# displayLCD.net
KiCad netlist of a schematic drawn in Altium Designer
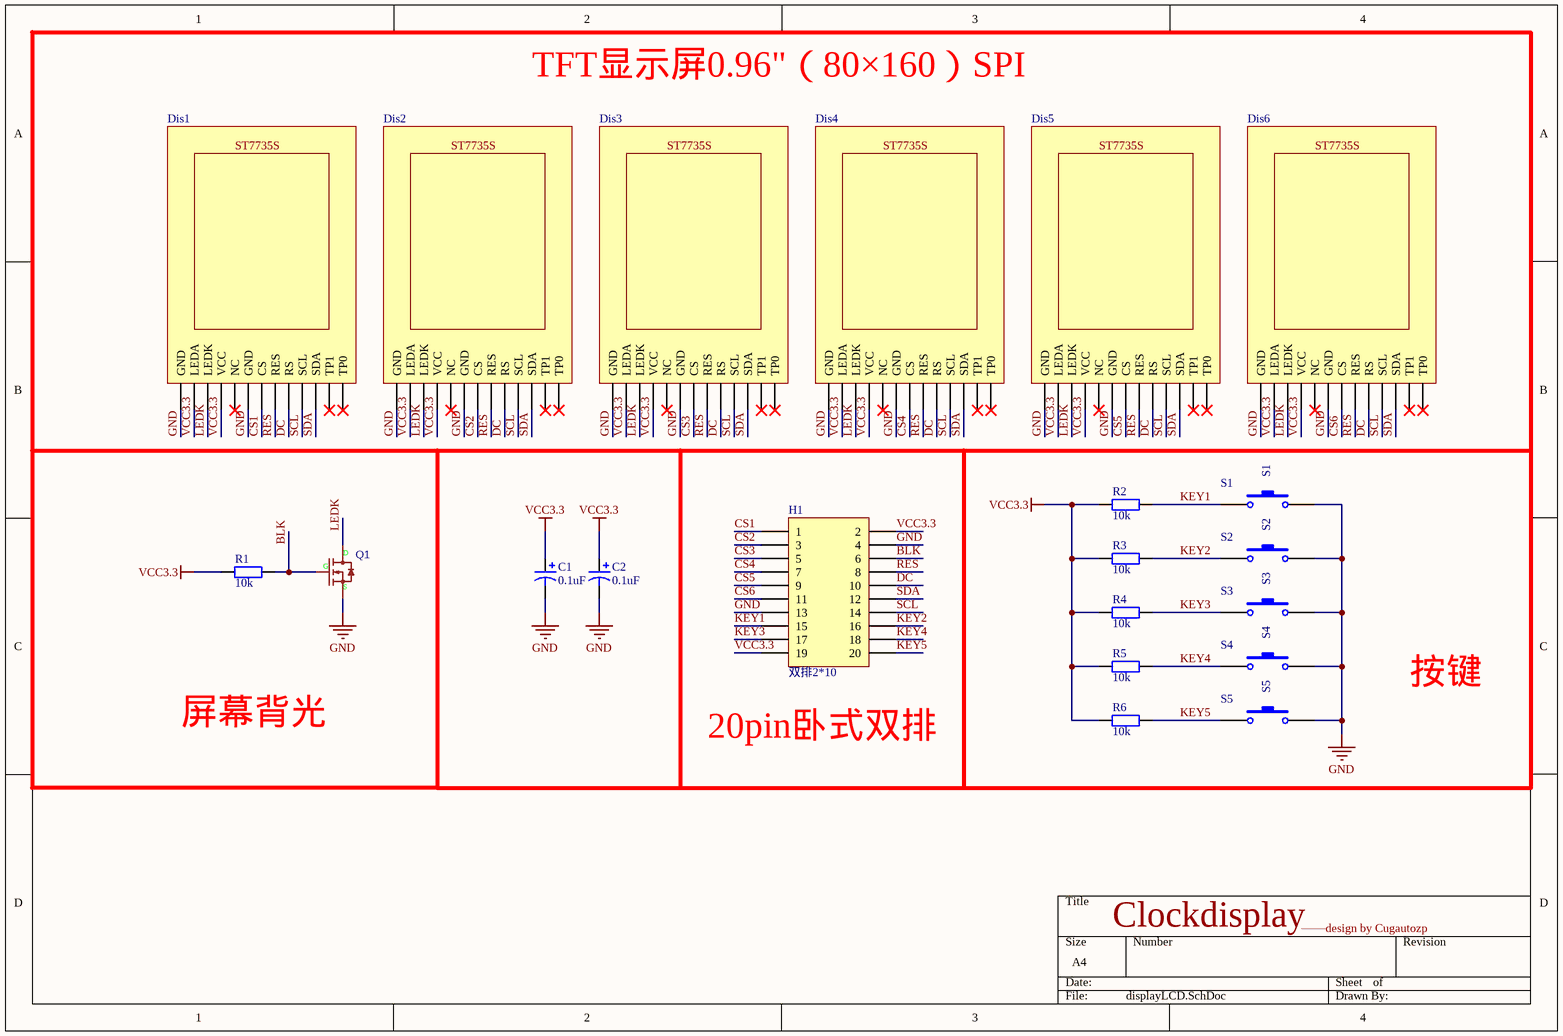
[diagram p0: displayLCD.SchDoc]

(export (version "E")
  (design (tool "Eeschema 10.0.6"))
  (components
    (comp (ref "C1")
      (value "0.1uF")
      (footprint "Cap0603")
      (description "Polarized Capacitor (Surface Mount)")
      (fields (field (name "PUBLISHER") "Altium Limited"))
      (libsource (lib "Miscellaneous Devices") (part "Cap Pol3"))
    )
    (comp (ref "C2")
      (value "0.1uF")
      (footprint "Cap0603")
      (description "Polarized Capacitor (Surface Mount)")
      (fields (field (name "PUBLISHER") "Altium Limited"))
      (libsource (lib "Miscellaneous Devices") (part "Cap Pol3"))
    )
    (comp (ref "Dis1")
      (value "LCD80*160")
      (footprint "LCD屏80*160")
      (libsource (lib "displayLCD") (part "LCD80*160"))
    )
    (comp (ref "Dis2")
      (value "LCD80*160")
      (footprint "LCD屏80*160")
      (libsource (lib "displayLCD") (part "LCD80*160"))
    )
    (comp (ref "Dis3")
      (value "LCD80*160")
      (footprint "LCD屏80*160")
      (libsource (lib "displayLCD") (part "LCD80*160"))
    )
    (comp (ref "Dis4")
      (value "LCD80*160")
      (footprint "LCD屏80*160")
      (libsource (lib "displayLCD") (part "LCD80*160"))
    )
    (comp (ref "Dis5")
      (value "LCD80*160")
      (footprint "LCD屏80*160")
      (libsource (lib "displayLCD") (part "LCD80*160"))
    )
    (comp (ref "Dis6")
      (value "LCD80*160")
      (footprint "LCD屏80*160")
      (libsource (lib "displayLCD") (part "LCD80*160"))
    )
    (comp (ref "H1") (value "双排2*10") (footprint "pin20双排母") (libsource (lib "displayLCD") (part "双排2*10")))
    (comp (ref "Q1")
      (value "LN4812LT1G")
      (footprint "sot23")
      (fields (field (name "BOM_SUPPLIER PART") "C559076") (field (name "CONTRIBUTOR") "LCSC"))
      (libsource (lib "displayLCD") (part "LN4812LT1G"))
    )
    (comp (ref "R1")
      (value "10k")
      (footprint "R0603")
      (description "Resistor")
      (fields (field (name "PUBLISHER") "Altium Limited"))
      (libsource (lib "Miscellaneous Devices") (part "Res2"))
    )
    (comp (ref "R2")
      (value "10k")
      (footprint "R0603")
      (description "Resistor")
      (fields (field (name "PUBLISHER") "Altium Limited"))
      (libsource (lib "Miscellaneous Devices") (part "Res2"))
    )
    (comp (ref "R3")
      (value "10k")
      (footprint "R0603")
      (description "Resistor")
      (fields (field (name "PUBLISHER") "Altium Limited"))
      (libsource (lib "Miscellaneous Devices") (part "Res2"))
    )
    (comp (ref "R4")
      (value "10k")
      (footprint "R0603")
      (description "Resistor")
      (fields (field (name "PUBLISHER") "Altium Limited"))
      (libsource (lib "Miscellaneous Devices") (part "Res2"))
    )
    (comp (ref "R5")
      (value "10k")
      (footprint "R0603")
      (description "Resistor")
      (fields (field (name "PUBLISHER") "Altium Limited"))
      (libsource (lib "Miscellaneous Devices") (part "Res2"))
    )
    (comp (ref "R6")
      (value "10k")
      (footprint "R0603")
      (description "Resistor")
      (fields (field (name "PUBLISHER") "Altium Limited"))
      (libsource (lib "Miscellaneous Devices") (part "Res2"))
    )
    (comp (ref "S1")
      (value "S1")
      (footprint "key(按键)")
      (description "Switch")
      (fields (field (name "PUBLISHER") "Altium Limited"))
      (libsource (lib "Miscellaneous Devices") (part "SW-PB"))
    )
    (comp (ref "S2")
      (value "S2")
      (footprint "key(按键)")
      (description "Switch")
      (fields (field (name "PUBLISHER") "Altium Limited"))
      (libsource (lib "Miscellaneous Devices") (part "SW-PB"))
    )
    (comp (ref "S3")
      (value "S3")
      (footprint "key(按键)")
      (description "Switch")
      (fields (field (name "PUBLISHER") "Altium Limited"))
      (libsource (lib "Miscellaneous Devices") (part "SW-PB"))
    )
    (comp (ref "S4")
      (value "S4")
      (footprint "key(按键)")
      (description "Switch")
      (fields (field (name "PUBLISHER") "Altium Limited"))
      (libsource (lib "Miscellaneous Devices") (part "SW-PB"))
    )
    (comp (ref "S5")
      (value "S5")
      (footprint "key(按键)")
      (description "Switch")
      (fields (field (name "PUBLISHER") "Altium Limited"))
      (libsource (lib "Miscellaneous Devices") (part "SW-PB"))
    )
  )
  (nets
    (net (code "1") (name "/BLK") (class "Default")
      (node (ref "H1") (pin "6") (pinfunction "6_6") (pintype "passive"))
      (node (ref "Q1") (pin "1") (pinfunction "G_1") (pintype "passive"))
      (node (ref "R1") (pin "2") (pinfunction "2_2") (pintype "passive"))
    )
    (net (code "2") (name "/CS1") (class "Default")
      (node (ref "Dis1") (pin "7") (pinfunction "CS_7") (pintype "passive"))
      (node (ref "H1") (pin "1") (pinfunction "1_1") (pintype "passive"))
    )
    (net (code "3") (name "/CS2") (class "Default")
      (node (ref "Dis2") (pin "7") (pinfunction "CS_7") (pintype "passive"))
      (node (ref "H1") (pin "3") (pinfunction "3_3") (pintype "passive"))
    )
    (net (code "4") (name "/CS3") (class "Default")
      (node (ref "Dis3") (pin "7") (pinfunction "CS_7") (pintype "passive"))
      (node (ref "H1") (pin "5") (pinfunction "5_5") (pintype "passive"))
    )
    (net (code "5") (name "/CS4") (class "Default")
      (node (ref "Dis4") (pin "7") (pinfunction "CS_7") (pintype "passive"))
      (node (ref "H1") (pin "7") (pinfunction "7_7") (pintype "passive"))
    )
    (net (code "6") (name "/CS5") (class "Default")
      (node (ref "Dis5") (pin "7") (pinfunction "CS_7") (pintype "passive"))
      (node (ref "H1") (pin "9") (pinfunction "9_9") (pintype "passive"))
    )
    (net (code "7") (name "/CS6") (class "Default")
      (node (ref "Dis6") (pin "7") (pinfunction "CS_7") (pintype "passive"))
      (node (ref "H1") (pin "11") (pinfunction "11_11") (pintype "passive"))
    )
    (net (code "8") (name "/DC") (class "Default")
      (node (ref "Dis1") (pin "5") (pinfunction "RS_5") (pintype "passive"))
      (node (ref "Dis2") (pin "5") (pinfunction "RS_5") (pintype "passive"))
      (node (ref "Dis3") (pin "5") (pinfunction "RS_5") (pintype "passive"))
      (node (ref "Dis4") (pin "5") (pinfunction "RS_5") (pintype "passive"))
      (node (ref "Dis5") (pin "5") (pinfunction "RS_5") (pintype "passive"))
      (node (ref "Dis6") (pin "5") (pinfunction "RS_5") (pintype "passive"))
      (node (ref "H1") (pin "10") (pinfunction "10_10") (pintype "passive"))
    )
    (net (code "9") (name "/KEY1") (class "Default")
      (node (ref "H1") (pin "15") (pinfunction "15_15") (pintype "passive"))
      (node (ref "R2") (pin "2") (pinfunction "2_2") (pintype "passive"))
      (node (ref "S1") (pin "1") (pinfunction "1_1") (pintype "passive"))
    )
    (net (code "10") (name "/KEY2") (class "Default")
      (node (ref "H1") (pin "16") (pinfunction "16_16") (pintype "passive"))
      (node (ref "R3") (pin "2") (pinfunction "2_2") (pintype "passive"))
      (node (ref "S2") (pin "1") (pinfunction "1_1") (pintype "passive"))
    )
    (net (code "11") (name "/KEY3") (class "Default")
      (node (ref "H1") (pin "17") (pinfunction "17_17") (pintype "passive"))
      (node (ref "R4") (pin "2") (pinfunction "2_2") (pintype "passive"))
      (node (ref "S3") (pin "1") (pinfunction "1_1") (pintype "passive"))
    )
    (net (code "12") (name "/KEY4") (class "Default")
      (node (ref "H1") (pin "18") (pinfunction "18_18") (pintype "passive"))
      (node (ref "R5") (pin "2") (pinfunction "2_2") (pintype "passive"))
      (node (ref "S4") (pin "1") (pinfunction "1_1") (pintype "passive"))
    )
    (net (code "13") (name "/KEY5") (class "Default")
      (node (ref "H1") (pin "20") (pinfunction "20_20") (pintype "passive"))
      (node (ref "R6") (pin "2") (pinfunction "2_2") (pintype "passive"))
      (node (ref "S5") (pin "1") (pinfunction "1_1") (pintype "passive"))
    )
    (net (code "14") (name "/LEDK") (class "Default")
      (node (ref "Dis1") (pin "11") (pinfunction "LEDK_11") (pintype "passive"))
      (node (ref "Dis2") (pin "11") (pinfunction "LEDK_11") (pintype "passive"))
      (node (ref "Dis3") (pin "11") (pinfunction "LEDK_11") (pintype "passive"))
      (node (ref "Dis4") (pin "11") (pinfunction "LEDK_11") (pintype "passive"))
      (node (ref "Dis5") (pin "11") (pinfunction "LEDK_11") (pintype "passive"))
      (node (ref "Dis6") (pin "11") (pinfunction "LEDK_11") (pintype "passive"))
      (node (ref "Q1") (pin "3") (pinfunction "D_3") (pintype "passive"))
    )
    (net (code "15") (name "/RES") (class "Default")
      (node (ref "Dis1") (pin "6") (pinfunction "RES_6") (pintype "passive"))
      (node (ref "Dis2") (pin "6") (pinfunction "RES_6") (pintype "passive"))
      (node (ref "Dis3") (pin "6") (pinfunction "RES_6") (pintype "passive"))
      (node (ref "Dis4") (pin "6") (pinfunction "RES_6") (pintype "passive"))
      (node (ref "Dis5") (pin "6") (pinfunction "RES_6") (pintype "passive"))
      (node (ref "Dis6") (pin "6") (pinfunction "RES_6") (pintype "passive"))
      (node (ref "H1") (pin "8") (pinfunction "8_8") (pintype "passive"))
    )
    (net (code "16") (name "/SCL") (class "Default")
      (node (ref "Dis1") (pin "4") (pinfunction "SCL_4") (pintype "passive"))
      (node (ref "Dis2") (pin "4") (pinfunction "SCL_4") (pintype "passive"))
      (node (ref "Dis3") (pin "4") (pinfunction "SCL_4") (pintype "passive"))
      (node (ref "Dis4") (pin "4") (pinfunction "SCL_4") (pintype "passive"))
      (node (ref "Dis5") (pin "4") (pinfunction "SCL_4") (pintype "passive"))
      (node (ref "Dis6") (pin "4") (pinfunction "SCL_4") (pintype "passive"))
      (node (ref "H1") (pin "14") (pinfunction "14_14") (pintype "passive"))
    )
    (net (code "17") (name "/SDA") (class "Default")
      (node (ref "Dis1") (pin "3") (pinfunction "SDA_3") (pintype "passive"))
      (node (ref "Dis2") (pin "3") (pinfunction "SDA_3") (pintype "passive"))
      (node (ref "Dis3") (pin "3") (pinfunction "SDA_3") (pintype "passive"))
      (node (ref "Dis4") (pin "3") (pinfunction "SDA_3") (pintype "passive"))
      (node (ref "Dis5") (pin "3") (pinfunction "SDA_3") (pintype "passive"))
      (node (ref "Dis6") (pin "3") (pinfunction "SDA_3") (pintype "passive"))
      (node (ref "H1") (pin "12") (pinfunction "12_12") (pintype "passive"))
    )
    (net (code "18") (name "GND") (class "Default")
      (node (ref "C1") (pin "2") (pinfunction "2_2") (pintype "passive"))
      (node (ref "C2") (pin "2") (pinfunction "2_2") (pintype "passive"))
      (node (ref "Dis1") (pin "13") (pinfunction "GND_13") (pintype "passive"))
      (node (ref "Dis1") (pin "8") (pinfunction "GND_8") (pintype "passive"))
      (node (ref "Dis2") (pin "13") (pinfunction "GND_13") (pintype "passive"))
      (node (ref "Dis2") (pin "8") (pinfunction "GND_8") (pintype "passive"))
      (node (ref "Dis3") (pin "13") (pinfunction "GND_13") (pintype "passive"))
      (node (ref "Dis3") (pin "8") (pinfunction "GND_8") (pintype "passive"))
      (node (ref "Dis4") (pin "13") (pinfunction "GND_13") (pintype "passive"))
      (node (ref "Dis4") (pin "8") (pinfunction "GND_8") (pintype "passive"))
      (node (ref "Dis5") (pin "13") (pinfunction "GND_13") (pintype "passive"))
      (node (ref "Dis5") (pin "8") (pinfunction "GND_8") (pintype "passive"))
      (node (ref "Dis6") (pin "13") (pinfunction "GND_13") (pintype "passive"))
      (node (ref "Dis6") (pin "8") (pinfunction "GND_8") (pintype "passive"))
      (node (ref "H1") (pin "13") (pinfunction "13_13") (pintype "passive"))
      (node (ref "H1") (pin "4") (pinfunction "4_4") (pintype "passive"))
      (node (ref "Q1") (pin "2") (pinfunction "S_2") (pintype "passive"))
      (node (ref "S1") (pin "2") (pinfunction "2_2") (pintype "passive"))
      (node (ref "S2") (pin "2") (pinfunction "2_2") (pintype "passive"))
      (node (ref "S3") (pin "2") (pinfunction "2_2") (pintype "passive"))
      (node (ref "S4") (pin "2") (pinfunction "2_2") (pintype "passive"))
      (node (ref "S5") (pin "2") (pinfunction "2_2") (pintype "passive"))
    )
    (net (code "19") (name "VCC3.3") (class "Default")
      (node (ref "C1") (pin "1") (pinfunction "1_1") (pintype "passive"))
      (node (ref "C2") (pin "1") (pinfunction "1_1") (pintype "passive"))
      (node (ref "Dis1") (pin "10") (pinfunction "VCC_10") (pintype "passive"))
      (node (ref "Dis1") (pin "12") (pinfunction "LEDA_12") (pintype "passive"))
      (node (ref "Dis2") (pin "10") (pinfunction "VCC_10") (pintype "passive"))
      (node (ref "Dis2") (pin "12") (pinfunction "LEDA_12") (pintype "passive"))
      (node (ref "Dis3") (pin "10") (pinfunction "VCC_10") (pintype "passive"))
      (node (ref "Dis3") (pin "12") (pinfunction "LEDA_12") (pintype "passive"))
      (node (ref "Dis4") (pin "10") (pinfunction "VCC_10") (pintype "passive"))
      (node (ref "Dis4") (pin "12") (pinfunction "LEDA_12") (pintype "passive"))
      (node (ref "Dis5") (pin "10") (pinfunction "VCC_10") (pintype "passive"))
      (node (ref "Dis5") (pin "12") (pinfunction "LEDA_12") (pintype "passive"))
      (node (ref "Dis6") (pin "10") (pinfunction "VCC_10") (pintype "passive"))
      (node (ref "Dis6") (pin "12") (pinfunction "LEDA_12") (pintype "passive"))
      (node (ref "H1") (pin "19") (pinfunction "19_19") (pintype "passive"))
      (node (ref "H1") (pin "2") (pinfunction "2_2") (pintype "passive"))
      (node (ref "R1") (pin "1") (pinfunction "1_1") (pintype "passive"))
      (node (ref "R2") (pin "1") (pinfunction "1_1") (pintype "passive"))
      (node (ref "R3") (pin "1") (pinfunction "1_1") (pintype "passive"))
      (node (ref "R4") (pin "1") (pinfunction "1_1") (pintype "passive"))
      (node (ref "R5") (pin "1") (pinfunction "1_1") (pintype "passive"))
      (node (ref "R6") (pin "1") (pinfunction "1_1") (pintype "passive"))
    )
    (net (code "20") (name "unconnected-(Dis1-NC-Pad9)") (class "Default")
      (node (ref "Dis1") (pin "9") (pinfunction "NC_9") (pintype "passive+no_connect"))
    )
    (net (code "21") (name "unconnected-(Dis1-TP0-Pad1)") (class "Default")
      (node (ref "Dis1") (pin "1") (pinfunction "TP0_1") (pintype "passive+no_connect"))
    )
    (net (code "22") (name "unconnected-(Dis1-TP1-Pad2)") (class "Default")
      (node (ref "Dis1") (pin "2") (pinfunction "TP1_2") (pintype "passive+no_connect"))
    )
    (net (code "23") (name "unconnected-(Dis2-NC-Pad9)") (class "Default")
      (node (ref "Dis2") (pin "9") (pinfunction "NC_9") (pintype "passive+no_connect"))
    )
    (net (code "24") (name "unconnected-(Dis2-TP0-Pad1)") (class "Default")
      (node (ref "Dis2") (pin "1") (pinfunction "TP0_1") (pintype "passive+no_connect"))
    )
    (net (code "25") (name "unconnected-(Dis2-TP1-Pad2)") (class "Default")
      (node (ref "Dis2") (pin "2") (pinfunction "TP1_2") (pintype "passive+no_connect"))
    )
    (net (code "26") (name "unconnected-(Dis3-NC-Pad9)") (class "Default")
      (node (ref "Dis3") (pin "9") (pinfunction "NC_9") (pintype "passive+no_connect"))
    )
    (net (code "27") (name "unconnected-(Dis3-TP0-Pad1)") (class "Default")
      (node (ref "Dis3") (pin "1") (pinfunction "TP0_1") (pintype "passive+no_connect"))
    )
    (net (code "28") (name "unconnected-(Dis3-TP1-Pad2)") (class "Default")
      (node (ref "Dis3") (pin "2") (pinfunction "TP1_2") (pintype "passive+no_connect"))
    )
    (net (code "29") (name "unconnected-(Dis4-NC-Pad9)") (class "Default")
      (node (ref "Dis4") (pin "9") (pinfunction "NC_9") (pintype "passive+no_connect"))
    )
    (net (code "30") (name "unconnected-(Dis4-TP0-Pad1)") (class "Default")
      (node (ref "Dis4") (pin "1") (pinfunction "TP0_1") (pintype "passive+no_connect"))
    )
    (net (code "31") (name "unconnected-(Dis4-TP1-Pad2)") (class "Default")
      (node (ref "Dis4") (pin "2") (pinfunction "TP1_2") (pintype "passive+no_connect"))
    )
    (net (code "32") (name "unconnected-(Dis5-NC-Pad9)") (class "Default")
      (node (ref "Dis5") (pin "9") (pinfunction "NC_9") (pintype "passive+no_connect"))
    )
    (net (code "33") (name "unconnected-(Dis5-TP0-Pad1)") (class "Default")
      (node (ref "Dis5") (pin "1") (pinfunction "TP0_1") (pintype "passive+no_connect"))
    )
    (net (code "34") (name "unconnected-(Dis5-TP1-Pad2)") (class "Default")
      (node (ref "Dis5") (pin "2") (pinfunction "TP1_2") (pintype "passive+no_connect"))
    )
    (net (code "35") (name "unconnected-(Dis6-NC-Pad9)") (class "Default")
      (node (ref "Dis6") (pin "9") (pinfunction "NC_9") (pintype "passive+no_connect"))
    )
    (net (code "36") (name "unconnected-(Dis6-TP0-Pad1)") (class "Default")
      (node (ref "Dis6") (pin "1") (pinfunction "TP0_1") (pintype "passive+no_connect"))
    )
    (net (code "37") (name "unconnected-(Dis6-TP1-Pad2)") (class "Default")
      (node (ref "Dis6") (pin "2") (pinfunction "TP1_2") (pintype "passive+no_connect"))
    )
  )
)
